# RobotCtrl_V2_Mother-board.net
KiCad netlist of a schematic drawn in Altium Designer
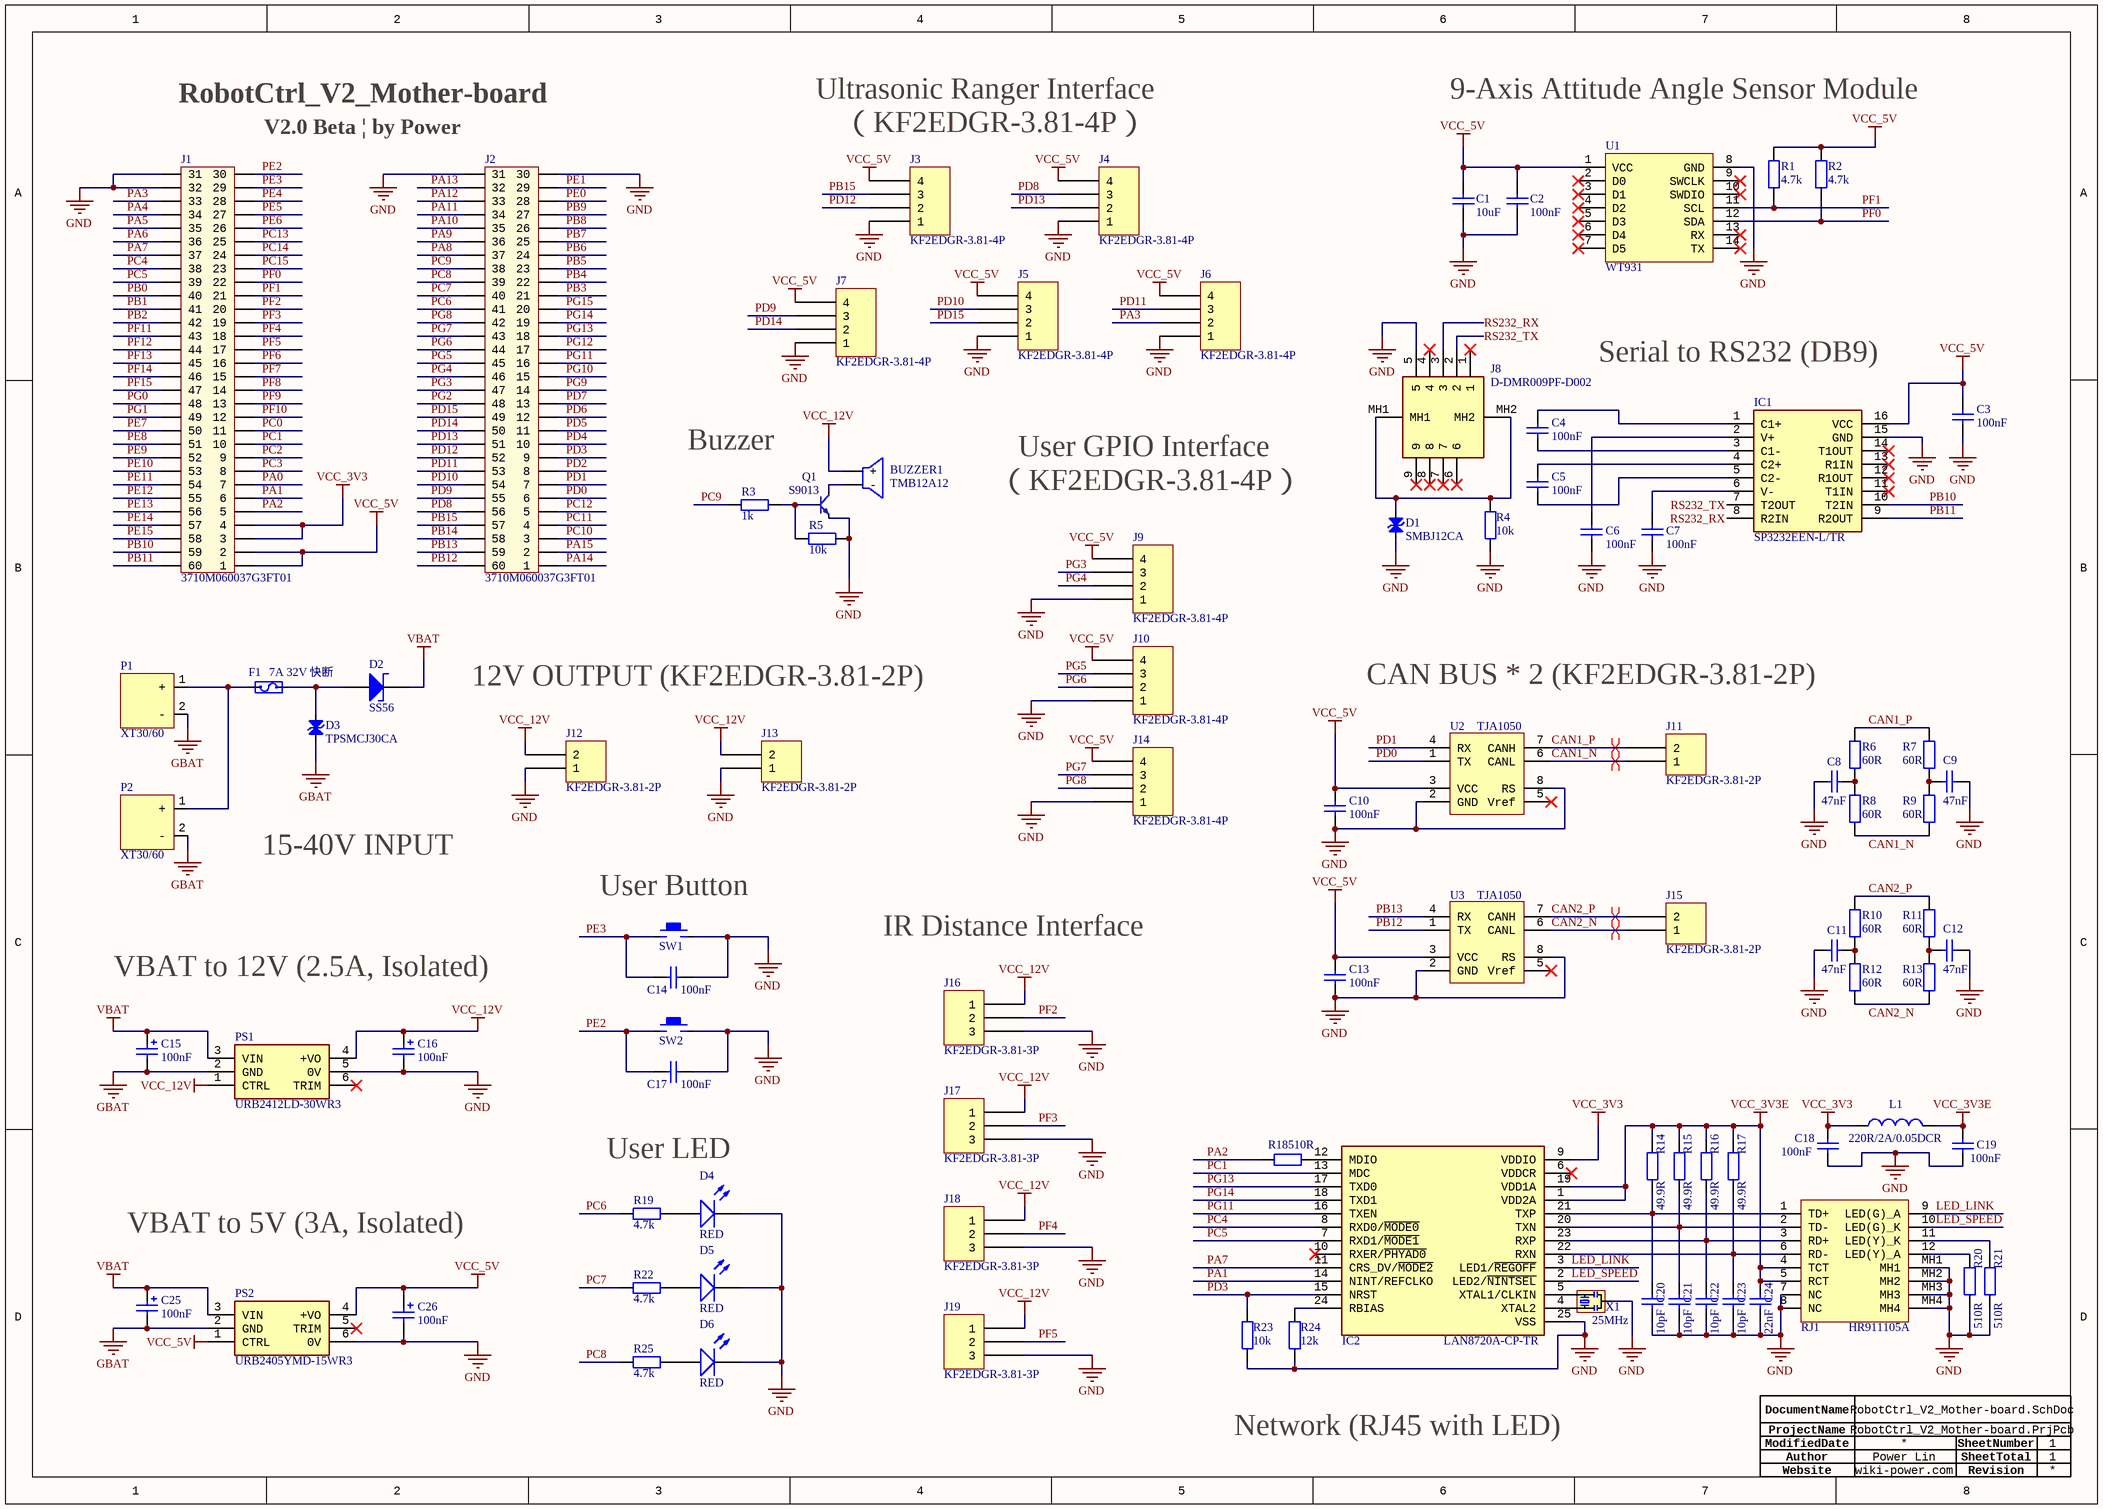
[diagram p0: RobotCtrl_V2_Mother-board.SchDoc]

(export (version "E")
  (design (tool "Eeschema 10.0.6"))
  (components
    (comp (ref "BUZZER1")
      (value "TMB12A12")
      (footprint "DIP,P=7.6mm")
      (description "TMB12A12 有源蜂鸣器")
      (libsource (lib "Power_Lib_Altium") (part "BUZZER"))
    )
    (comp (ref "C1")
      (value "10uF")
      (footprint "CAP-0603")
      (description "贴片电容")
      (libsource (lib "Power_Lib_Altium") (part "CAP"))
    )
    (comp (ref "C2")
      (value "100nF")
      (footprint "CAP-0603")
      (description "贴片电容")
      (libsource (lib "Power_Lib_Altium") (part "CAP"))
    )
    (comp (ref "C3")
      (value "100nF")
      (footprint "CAP-0603")
      (description "贴片电容")
      (libsource (lib "Power_Lib_Altium") (part "CAP"))
    )
    (comp (ref "C4")
      (value "100nF")
      (footprint "CAP-0603")
      (description "贴片电容")
      (libsource (lib "Power_Lib_Altium") (part "CAP"))
    )
    (comp (ref "C5")
      (value "100nF")
      (footprint "CAP-0603")
      (description "贴片电容")
      (libsource (lib "Power_Lib_Altium") (part "CAP"))
    )
    (comp (ref "C6")
      (value "100nF")
      (footprint "CAP-0603")
      (description "贴片电容")
      (libsource (lib "Power_Lib_Altium") (part "CAP"))
    )
    (comp (ref "C7")
      (value "100nF")
      (footprint "CAP-0603")
      (description "贴片电容")
      (libsource (lib "Power_Lib_Altium") (part "CAP"))
    )
    (comp (ref "C8")
      (value "47nF")
      (footprint "CAP-0603")
      (description "贴片电容")
      (libsource (lib "Power_Lib_Altium") (part "CAP"))
    )
    (comp (ref "C9")
      (value "47nF")
      (footprint "CAP-0603")
      (description "贴片电容")
      (libsource (lib "Power_Lib_Altium") (part "CAP"))
    )
    (comp (ref "C10")
      (value "100nF")
      (footprint "CAP-0603")
      (description "贴片电容")
      (libsource (lib "Power_Lib_Altium") (part "CAP"))
    )
    (comp (ref "C11")
      (value "47nF")
      (footprint "CAP-0603")
      (description "贴片电容")
      (libsource (lib "Power_Lib_Altium") (part "CAP"))
    )
    (comp (ref "C12")
      (value "47nF")
      (footprint "CAP-0603")
      (description "贴片电容")
      (libsource (lib "Power_Lib_Altium") (part "CAP"))
    )
    (comp (ref "C13")
      (value "100nF")
      (footprint "CAP-0603")
      (description "贴片电容")
      (libsource (lib "Power_Lib_Altium") (part "CAP"))
    )
    (comp (ref "C14")
      (value "100nF")
      (footprint "CAP-0603")
      (description "贴片电容")
      (libsource (lib "Power_Lib_Altium") (part "CAP"))
    )
    (comp (ref "C15")
      (value "100nF")
      (footprint "CAP-AUX-3216")
      (description "KM101M050F115A")
      (libsource (lib "Power_Lib_Altium") (part "CAP-POL"))
    )
    (comp (ref "C16")
      (value "100nF")
      (footprint "CAP-AUX-3216")
      (description "KM101M050F115A")
      (libsource (lib "Power_Lib_Altium") (part "CAP-POL"))
    )
    (comp (ref "C17")
      (value "100nF")
      (footprint "CAP-0603")
      (description "贴片电容")
      (libsource (lib "Power_Lib_Altium") (part "CAP"))
    )
    (comp (ref "C18")
      (value "100nF")
      (footprint "CAP-0603")
      (description "贴片电容")
      (libsource (lib "Power_Lib_Altium") (part "CAP"))
    )
    (comp (ref "C19")
      (value "100nF")
      (footprint "CAP-0603")
      (description "贴片电容")
      (libsource (lib "Power_Lib_Altium") (part "CAP"))
    )
    (comp (ref "C20")
      (value "10pF")
      (footprint "CAP-0603")
      (description "贴片电容")
      (libsource (lib "Power_Lib_Altium") (part "CAP"))
    )
    (comp (ref "C21")
      (value "10pF")
      (footprint "CAP-0603")
      (description "贴片电容")
      (libsource (lib "Power_Lib_Altium") (part "CAP"))
    )
    (comp (ref "C22")
      (value "10pF")
      (footprint "CAP-0603")
      (description "贴片电容")
      (libsource (lib "Power_Lib_Altium") (part "CAP"))
    )
    (comp (ref "C23")
      (value "10pF")
      (footprint "CAP-0603")
      (description "贴片电容")
      (libsource (lib "Power_Lib_Altium") (part "CAP"))
    )
    (comp (ref "C24")
      (value "22nF")
      (footprint "CAP-0603")
      (description "贴片电容")
      (libsource (lib "Power_Lib_Altium") (part "CAP"))
    )
    (comp (ref "C25")
      (value "100nF")
      (footprint "CAP-AUX-3216")
      (description "KM101M050F115A")
      (libsource (lib "Power_Lib_Altium") (part "CAP-POL"))
    )
    (comp (ref "C26")
      (value "100nF")
      (footprint "CAP-AUX-3216")
      (description "KM101M050F115A")
      (libsource (lib "Power_Lib_Altium") (part "CAP-POL"))
    )
    (comp (ref "D1")
      (value "SMBJ12CA")
      (footprint "DO-214AA/SMB")
      (libsource (lib "Power_Lib_Altium") (part "TVS_C"))
    )
    (comp (ref "D2")
      (value "SS56")
      (footprint "DO-214AB/SMC")
      (description "肖特基二极管")
      (libsource (lib "Power_Lib_Altium") (part "DIODE_Schottky"))
    )
    (comp (ref "D3")
      (value "TPSMCJ30CA")
      (footprint "DO-214AB/SMC")
      (libsource (lib "Power_Lib_Altium") (part "TVS_C"))
    )
    (comp (ref "D4")
      (value "RED")
      (footprint "LED-0603")
      (description "发光二极管")
      (libsource (lib "Power_Lib_Altium") (part "LED"))
    )
    (comp (ref "D5")
      (value "RED")
      (footprint "LED-0603")
      (description "发光二极管")
      (libsource (lib "Power_Lib_Altium") (part "LED"))
    )
    (comp (ref "D6")
      (value "RED")
      (footprint "LED-0603")
      (description "发光二极管")
      (libsource (lib "Power_Lib_Altium") (part "LED"))
    )
    (comp (ref "F1")
      (value "7A 32V 快断")
      (footprint "FUSE_1206")
      (description "0437007.WR")
      (libsource (lib "Power_Lib_Altium") (part "Fuse"))
    )
    (comp (ref "IC1")
      (value "SP3232EEN-L/TR")
      (footprint "SOIC-16_150mil")
      (description "RS232 芯片")
      (fields (field (name "MOUSER PART NUMBER") "701-SP3232EEN-L/TR"))
      (libsource (lib "Power_Lib_Altium") (part "SP3232EEN"))
    )
    (comp (ref "IC2")
      (value "LAN8720A-CP-TR")
      (footprint "QFN-24-4x4")
      (description "Integrated Circuit")
      (fields (field (name "MOUSER PART NUMBER") "886-LAN8720A-CP-TR"))
      (libsource (lib "Power_Lib_Altium") (part "LAN8720A-CP-TR"))
    )
    (comp (ref "J1")
      (value "3710M060037G3FT01")
      (footprint "3710M060037G3FT01")
      (description "B2B Connector")
      (libsource (lib "Power_Lib_Altium") (part "3710M/F"))
    )
    (comp (ref "J2")
      (value "3710M060037G3FT01")
      (footprint "3710M060037G3FT01")
      (description "B2B Connector")
      (libsource (lib "Power_Lib_Altium") (part "3710M/F"))
    )
    (comp (ref "J3")
      (value "KF2EDGR-3.81-4P")
      (footprint "FCI 06-381-4PIN")
      (description "TERM BLOCK HDR 4POS 90DEG 3.81MM")
      (fields (field (name "PART NUMBER") "OQ0432510000G") (field (name "MANUFACTURER") "Amphenol Anytek"))
      (libsource (lib "Power_Lib_Altium") (part "KF2EDGR-3.81-4P"))
    )
    (comp (ref "J4")
      (value "KF2EDGR-3.81-4P")
      (footprint "FCI 06-381-4PIN")
      (description "TERM BLOCK HDR 4POS 90DEG 3.81MM")
      (fields (field (name "PART NUMBER") "OQ0432510000G") (field (name "MANUFACTURER") "Amphenol Anytek"))
      (libsource (lib "Power_Lib_Altium") (part "KF2EDGR-3.81-4P"))
    )
    (comp (ref "J5")
      (value "KF2EDGR-3.81-4P")
      (footprint "FCI 06-381-4PIN")
      (description "TERM BLOCK HDR 4POS 90DEG 3.81MM")
      (fields (field (name "PART NUMBER") "OQ0432510000G") (field (name "MANUFACTURER") "Amphenol Anytek"))
      (libsource (lib "Power_Lib_Altium") (part "KF2EDGR-3.81-4P"))
    )
    (comp (ref "J6")
      (value "KF2EDGR-3.81-4P")
      (footprint "FCI 06-381-4PIN")
      (description "TERM BLOCK HDR 4POS 90DEG 3.81MM")
      (fields (field (name "PART NUMBER") "OQ0432510000G") (field (name "MANUFACTURER") "Amphenol Anytek"))
      (libsource (lib "Power_Lib_Altium") (part "KF2EDGR-3.81-4P"))
    )
    (comp (ref "J7")
      (value "KF2EDGR-3.81-4P")
      (footprint "FCI 06-381-4PIN")
      (description "TERM BLOCK HDR 4POS 90DEG 3.81MM")
      (fields (field (name "PART NUMBER") "OQ0432510000G") (field (name "MANUFACTURER") "Amphenol Anytek"))
      (libsource (lib "Power_Lib_Altium") (part "KF2EDGR-3.81-4P"))
    )
    (comp (ref "J8")
      (value "D-DMR009PF-D002")
      (footprint "Through Hole,P=2.77mm")
      (description "D-Sub 连接器")
      (fields
        (field (name "MANUFACTURER_PART_NUMBER") "5747844-5")
        (field (name "MOUSER PART NUMBER") "571-5747844-5")
      )
      (libsource (lib "Power_Lib_Altium") (part "DB9"))
    )
    (comp (ref "J9")
      (value "KF2EDGR-3.81-4P")
      (footprint "FCI 06-381-4PIN")
      (description "TERM BLOCK HDR 4POS 90DEG 3.81MM")
      (fields (field (name "PART NUMBER") "OQ0432510000G") (field (name "MANUFACTURER") "Amphenol Anytek"))
      (libsource (lib "Power_Lib_Altium") (part "KF2EDGR-3.81-4P"))
    )
    (comp (ref "J10")
      (value "KF2EDGR-3.81-4P")
      (footprint "FCI 06-381-4PIN")
      (description "TERM BLOCK HDR 4POS 90DEG 3.81MM")
      (fields (field (name "PART NUMBER") "OQ0432510000G") (field (name "MANUFACTURER") "Amphenol Anytek"))
      (libsource (lib "Power_Lib_Altium") (part "KF2EDGR-3.81-4P"))
    )
    (comp (ref "J11")
      (value "KF2EDGR-3.81-2P")
      (footprint "FCI 06-381-2PIN")
      (description "TERM BLOCK HDR 2POS 90DEG 3.81MM")
      (fields (field (name "PART NUMBER") "OQ0232510000G") (field (name "MANUFACTURER") "Amphenol Anytek"))
      (libsource (lib "Power_Lib_Altium") (part "KF2EDGR-3.81-2P"))
    )
    (comp (ref "J12")
      (value "KF2EDGR-3.81-2P")
      (footprint "FCI 06-381-2PIN")
      (description "TERM BLOCK HDR 2POS 90DEG 3.81MM")
      (fields (field (name "PART NUMBER") "OQ0232510000G") (field (name "MANUFACTURER") "Amphenol Anytek"))
      (libsource (lib "Power_Lib_Altium") (part "KF2EDGR-3.81-2P"))
    )
    (comp (ref "J13")
      (value "KF2EDGR-3.81-2P")
      (footprint "FCI 06-381-2PIN")
      (description "TERM BLOCK HDR 2POS 90DEG 3.81MM")
      (fields (field (name "PART NUMBER") "OQ0232510000G") (field (name "MANUFACTURER") "Amphenol Anytek"))
      (libsource (lib "Power_Lib_Altium") (part "KF2EDGR-3.81-2P"))
    )
    (comp (ref "J14")
      (value "KF2EDGR-3.81-4P")
      (footprint "FCI 06-381-4PIN")
      (description "TERM BLOCK HDR 4POS 90DEG 3.81MM")
      (fields (field (name "PART NUMBER") "OQ0432510000G") (field (name "MANUFACTURER") "Amphenol Anytek"))
      (libsource (lib "Power_Lib_Altium") (part "KF2EDGR-3.81-4P"))
    )
    (comp (ref "J15")
      (value "KF2EDGR-3.81-2P")
      (footprint "FCI 06-381-2PIN")
      (description "TERM BLOCK HDR 2POS 90DEG 3.81MM")
      (fields (field (name "PART NUMBER") "OQ0232510000G") (field (name "MANUFACTURER") "Amphenol Anytek"))
      (libsource (lib "Power_Lib_Altium") (part "KF2EDGR-3.81-2P"))
    )
    (comp (ref "J16")
      (value "KF2EDGR-3.81-3P")
      (footprint "FCI 06-381-3PIN")
      (description "TERM BLOCK HDR 3POS 90DEG 3.81MM")
      (fields (field (name "MANUFACTURER") "Amphenol Anytek") (field (name "PART NUMBER") "OQ0332510000G"))
      (libsource (lib "Power_Lib_Altium") (part "KF2EDGR-3.81-3P"))
    )
    (comp (ref "J17")
      (value "KF2EDGR-3.81-3P")
      (footprint "FCI 06-381-3PIN")
      (description "TERM BLOCK HDR 3POS 90DEG 3.81MM")
      (fields (field (name "MANUFACTURER") "Amphenol Anytek") (field (name "PART NUMBER") "OQ0332510000G"))
      (libsource (lib "Power_Lib_Altium") (part "KF2EDGR-3.81-3P"))
    )
    (comp (ref "J18")
      (value "KF2EDGR-3.81-3P")
      (footprint "FCI 06-381-3PIN")
      (description "TERM BLOCK HDR 3POS 90DEG 3.81MM")
      (fields (field (name "MANUFACTURER") "Amphenol Anytek") (field (name "PART NUMBER") "OQ0332510000G"))
      (libsource (lib "Power_Lib_Altium") (part "KF2EDGR-3.81-3P"))
    )
    (comp (ref "J19")
      (value "KF2EDGR-3.81-3P")
      (footprint "FCI 06-381-3PIN")
      (description "TERM BLOCK HDR 3POS 90DEG 3.81MM")
      (fields (field (name "MANUFACTURER") "Amphenol Anytek") (field (name "PART NUMBER") "OQ0332510000G"))
      (libsource (lib "Power_Lib_Altium") (part "KF2EDGR-3.81-3P"))
    )
    (comp (ref "L1")
      (value "220R/2A/0.05DCR")
      (footprint "L-0603")
      (description "BLM18KG221SN1D")
      (libsource (lib "Power_Lib_Altium") (part "BEAD"))
    )
    (comp (ref "P1")
      (value "XT30/60")
      (footprint "XT60PW-M")
      (libsource (lib "Power_Lib_Altium") (part "XT30/60"))
    )
    (comp (ref "P2")
      (value "XT30/60")
      (footprint "XT60PW-M")
      (libsource (lib "Power_Lib_Altium") (part "XT30/60"))
    )
    (comp (ref "PS1")
      (value "URB2412LD-30WR3")
      (footprint "URB2412LD30WR3")
      (description "金升阳隔离电源")
      (fields (field (name "MANUFACTURER_PART_NUMBER") "URB2412LD-30WHR3"))
      (libsource (lib "Power_Lib_Altium") (part "URB2412LD-30WR3"))
    )
    (comp (ref "PS2")
      (value "URB2405YMD-15WR3")
      (footprint "URB2405YMD15WR3")
      (description "金升阳隔离电源")
      (fields (field (name "MANUFACTURER_PART_NUMBER") "URB2405YMD-10WR3"))
      (libsource (lib "Power_Lib_Altium") (part "URB2405YMD-15WR3"))
    )
    (comp (ref "Q1")
      (value "S9013")
      (footprint "SOT-23-3")
      (libsource (lib "Power_Lib_Altium") (part "BJT_NPN"))
    )
    (comp (ref "R1")
      (value "4.7k")
      (footprint "R-0603")
      (description "贴片电阻")
      (libsource (lib "") (part "RES_1"))
    )
    (comp (ref "R2")
      (value "4.7k")
      (footprint "R-0603")
      (description "贴片电阻")
      (libsource (lib "") (part "RES_1"))
    )
    (comp (ref "R3")
      (value "1k")
      (footprint "R-0603")
      (description "贴片电阻")
      (libsource (lib "") (part "RES_3"))
    )
    (comp (ref "R4")
      (value "10k")
      (footprint "R-0603")
      (description "贴片电阻")
      (libsource (lib "") (part "RES_1"))
    )
    (comp (ref "R5")
      (value "10k")
      (footprint "R-0603")
      (description "贴片电阻")
      (libsource (lib "") (part "RES_2"))
    )
    (comp (ref "R6")
      (value "60R")
      (footprint "R-0603")
      (description "贴片电阻")
      (libsource (lib "Power_Lib_Altium") (part "RES"))
    )
    (comp (ref "R7")
      (value "60R")
      (footprint "R-0603")
      (description "贴片电阻")
      (libsource (lib "") (part "RES_1"))
    )
    (comp (ref "R8")
      (value "60R")
      (footprint "R-0603")
      (description "贴片电阻")
      (libsource (lib "Power_Lib_Altium") (part "RES"))
    )
    (comp (ref "R9")
      (value "60R")
      (footprint "R-0603")
      (description "贴片电阻")
      (libsource (lib "") (part "RES_1"))
    )
    (comp (ref "R10")
      (value "60R")
      (footprint "R-0603")
      (description "贴片电阻")
      (libsource (lib "Power_Lib_Altium") (part "RES"))
    )
    (comp (ref "R11")
      (value "60R")
      (footprint "R-0603")
      (description "贴片电阻")
      (libsource (lib "") (part "RES_1"))
    )
    (comp (ref "R12")
      (value "60R")
      (footprint "R-0603")
      (description "贴片电阻")
      (libsource (lib "Power_Lib_Altium") (part "RES"))
    )
    (comp (ref "R13")
      (value "60R")
      (footprint "R-0603")
      (description "贴片电阻")
      (libsource (lib "") (part "RES_1"))
    )
    (comp (ref "R14")
      (value "49.9R")
      (footprint "R-0603")
      (description "贴片电阻")
      (libsource (lib "") (part "RES_1"))
    )
    (comp (ref "R15")
      (value "49.9R")
      (footprint "R-0603")
      (description "贴片电阻")
      (libsource (lib "") (part "RES_1"))
    )
    (comp (ref "R16")
      (value "49.9R")
      (footprint "R-0603")
      (description "贴片电阻")
      (libsource (lib "") (part "RES_1"))
    )
    (comp (ref "R17")
      (value "49.9R")
      (footprint "R-0603")
      (description "贴片电阻")
      (libsource (lib "") (part "RES_1"))
    )
    (comp (ref "R18")
      (value "510R")
      (footprint "R-0603")
      (description "贴片电阻")
      (libsource (lib "") (part "RES_2"))
    )
    (comp (ref "R19")
      (value "4.7k")
      (footprint "R-0603")
      (description "贴片电阻")
      (libsource (lib "") (part "RES_2"))
    )
    (comp (ref "R20")
      (value "510R")
      (footprint "R-0603")
      (description "贴片电阻")
      (libsource (lib "") (part "RES_1"))
    )
    (comp (ref "R21")
      (value "510R")
      (footprint "R-0603")
      (description "贴片电阻")
      (libsource (lib "") (part "RES_1"))
    )
    (comp (ref "R22")
      (value "4.7k")
      (footprint "R-0603")
      (description "贴片电阻")
      (libsource (lib "") (part "RES_2"))
    )
    (comp (ref "R23")
      (value "10k")
      (footprint "R-0603")
      (description "贴片电阻")
      (libsource (lib "Power_Lib_Altium") (part "RES"))
    )
    (comp (ref "R24")
      (value "12k")
      (footprint "R-0603")
      (description "贴片电阻")
      (libsource (lib "Power_Lib_Altium") (part "RES"))
    )
    (comp (ref "R25")
      (value "4.7k")
      (footprint "R-0603")
      (description "贴片电阻")
      (libsource (lib "") (part "RES_2"))
    )
    (comp (ref "RJ1")
      (value "HR911105A")
      (footprint "HR911105A")
      (libsource (lib "Power_Lib_Altium") (part "RJ45_LED"))
    )
    (comp (ref "SW1")
      (value "KEY")
      (footprint "KEY-4P-4.2*3.4*2.5")
      (description "按键开关")
      (libsource (lib "Power_Lib_Altium") (part "KEY"))
    )
    (comp (ref "SW2")
      (value "KEY")
      (footprint "KEY-4P-4.2*3.4*2.5")
      (description "按键开关")
      (libsource (lib "Power_Lib_Altium") (part "KEY"))
    )
    (comp (ref "U1")
      (value "WT931")
      (footprint "WT931")
      (description "陀螺仪模组")
      (libsource (lib "Power_Lib_Altium") (part "WT931"))
    )
    (comp (ref "U2")
      (value "TJA1050")
      (footprint "SOIC_8")
      (description "CAN 控制器（5V）")
      (libsource (lib "Power_Lib_Altium") (part "TJA1050"))
    )
    (comp (ref "U3")
      (value "TJA1050")
      (footprint "SOIC_8")
      (description "CAN 控制器（5V）")
      (libsource (lib "Power_Lib_Altium") (part "TJA1050"))
    )
    (comp (ref "X1")
      (value "25MHz")
      (footprint "SMD3213-3P")
      (description "CSTCE25M00G51-R0")
      (libsource (lib "Power_Lib_Altium") (part "XTAL"))
    )
  )
  (nets
    (net (code "1") (name "/CAN1_N") (class "Default")
      (node (ref "J11") (pin "1") (pinfunction "1_1") (pintype "passive"))
      (node (ref "R8") (pin "2") (pinfunction "2_2") (pintype "passive"))
      (node (ref "R9") (pin "1") (pinfunction "1_1") (pintype "passive"))
      (node (ref "U2") (pin "6") (pinfunction "CANL_6") (pintype "passive"))
    )
    (net (code "2") (name "/CAN1_P") (class "Default")
      (node (ref "J11") (pin "2") (pinfunction "2_2") (pintype "passive"))
      (node (ref "R6") (pin "1") (pinfunction "1_1") (pintype "passive"))
      (node (ref "R7") (pin "2") (pinfunction "2_2") (pintype "passive"))
      (node (ref "U2") (pin "7") (pinfunction "CANH_7") (pintype "passive"))
    )
    (net (code "3") (name "/CAN2_N") (class "Default")
      (node (ref "J15") (pin "1") (pinfunction "1_1") (pintype "passive"))
      (node (ref "R12") (pin "2") (pinfunction "2_2") (pintype "passive"))
      (node (ref "R13") (pin "1") (pinfunction "1_1") (pintype "passive"))
      (node (ref "U3") (pin "6") (pinfunction "CANL_6") (pintype "passive"))
    )
    (net (code "4") (name "/CAN2_P") (class "Default")
      (node (ref "J15") (pin "2") (pinfunction "2_2") (pintype "passive"))
      (node (ref "R10") (pin "1") (pinfunction "1_1") (pintype "passive"))
      (node (ref "R11") (pin "2") (pinfunction "2_2") (pintype "passive"))
      (node (ref "U3") (pin "7") (pinfunction "CANH_7") (pintype "passive"))
    )
    (net (code "5") (name "/LED_LINK") (class "Default")
      (node (ref "IC2") (pin "3") (pinfunction "LED1/~{REGOFF}_3") (pintype "passive"))
      (node (ref "RJ1") (pin "9") (pinfunction "LED(G)_A_9") (pintype "passive"))
    )
    (net (code "6") (name "/LED_SPEED") (class "Default")
      (node (ref "IC2") (pin "2") (pinfunction "LED2/~{NINTSEL}_2") (pintype "passive"))
      (node (ref "RJ1") (pin "10") (pinfunction "LED(G)_K_10") (pintype "passive"))
    )
    (net (code "7") (name "/PA0") (class "Default")
      (node (ref "J1") (pin "7") (pinfunction "7_7") (pintype "passive"))
    )
    (net (code "8") (name "/PA1") (class "Default")
      (node (ref "IC2") (pin "14") (pinfunction "NINT/REFCLKO_14") (pintype "passive"))
      (node (ref "J1") (pin "6") (pinfunction "6_6") (pintype "passive"))
    )
    (net (code "9") (name "/PA2") (class "Default")
      (node (ref "J1") (pin "5") (pinfunction "5_5") (pintype "passive"))
      (node (ref "R18") (pin "2") (pinfunction "2_2") (pintype "passive"))
    )
    (net (code "10") (name "/PA3") (class "Default")
      (node (ref "J1") (pin "33") (pinfunction "33_33") (pintype "passive"))
      (node (ref "J6") (pin "2") (pinfunction "2_2") (pintype "passive"))
    )
    (net (code "11") (name "/PA4") (class "Default")
      (node (ref "J1") (pin "34") (pinfunction "34_34") (pintype "passive"))
    )
    (net (code "12") (name "/PA5") (class "Default")
      (node (ref "J1") (pin "35") (pinfunction "35_35") (pintype "passive"))
    )
    (net (code "13") (name "/PA6") (class "Default")
      (node (ref "J1") (pin "36") (pinfunction "36_36") (pintype "passive"))
    )
    (net (code "14") (name "/PA7") (class "Default")
      (node (ref "IC2") (pin "11") (pinfunction "CRS_DV/~{MODE2}_11") (pintype "passive"))
      (node (ref "J1") (pin "37") (pinfunction "37_37") (pintype "passive"))
    )
    (net (code "15") (name "/PA8") (class "Default")
      (node (ref "J2") (pin "37") (pinfunction "37_37") (pintype "passive"))
    )
    (net (code "16") (name "/PA9") (class "Default")
      (node (ref "J2") (pin "36") (pinfunction "36_36") (pintype "passive"))
    )
    (net (code "17") (name "/PA10") (class "Default")
      (node (ref "J2") (pin "35") (pinfunction "35_35") (pintype "passive"))
    )
    (net (code "18") (name "/PA11") (class "Default")
      (node (ref "J2") (pin "34") (pinfunction "34_34") (pintype "passive"))
    )
    (net (code "19") (name "/PA12") (class "Default")
      (node (ref "J2") (pin "33") (pinfunction "33_33") (pintype "passive"))
    )
    (net (code "20") (name "/PA13") (class "Default")
      (node (ref "J2") (pin "32") (pinfunction "32_32") (pintype "passive"))
    )
    (net (code "21") (name "/PA14") (class "Default")
      (node (ref "J2") (pin "1") (pinfunction "1_1") (pintype "passive"))
    )
    (net (code "22") (name "/PA15") (class "Default")
      (node (ref "J2") (pin "2") (pinfunction "2_2") (pintype "passive"))
    )
    (net (code "23") (name "/PB0") (class "Default")
      (node (ref "J1") (pin "40") (pinfunction "40_40") (pintype "passive"))
    )
    (net (code "24") (name "/PB1") (class "Default")
      (node (ref "J1") (pin "41") (pinfunction "41_41") (pintype "passive"))
    )
    (net (code "25") (name "/PB2") (class "Default")
      (node (ref "J1") (pin "42") (pinfunction "42_42") (pintype "passive"))
    )
    (net (code "26") (name "/PB3") (class "Default")
      (node (ref "J2") (pin "21") (pinfunction "21_21") (pintype "passive"))
    )
    (net (code "27") (name "/PB4") (class "Default")
      (node (ref "J2") (pin "22") (pinfunction "22_22") (pintype "passive"))
    )
    (net (code "28") (name "/PB5") (class "Default")
      (node (ref "J2") (pin "23") (pinfunction "23_23") (pintype "passive"))
    )
    (net (code "29") (name "/PB6") (class "Default")
      (node (ref "J2") (pin "24") (pinfunction "24_24") (pintype "passive"))
    )
    (net (code "30") (name "/PB7") (class "Default")
      (node (ref "J2") (pin "25") (pinfunction "25_25") (pintype "passive"))
    )
    (net (code "31") (name "/PB8") (class "Default")
      (node (ref "J2") (pin "26") (pinfunction "26_26") (pintype "passive"))
    )
    (net (code "32") (name "/PB9") (class "Default")
      (node (ref "J2") (pin "27") (pinfunction "27_27") (pintype "passive"))
    )
    (net (code "33") (name "/PB10") (class "Default")
      (node (ref "IC1") (pin "10") (pinfunction "T2IN_10") (pintype "passive"))
      (node (ref "J1") (pin "59") (pinfunction "59_59") (pintype "passive"))
    )
    (net (code "34") (name "/PB11") (class "Default")
      (node (ref "IC1") (pin "9") (pinfunction "R2OUT_9") (pintype "passive"))
      (node (ref "J1") (pin "60") (pinfunction "60_60") (pintype "passive"))
    )
    (net (code "35") (name "/PB12") (class "Default")
      (node (ref "J2") (pin "60") (pinfunction "60_60") (pintype "passive"))
      (node (ref "U3") (pin "1") (pinfunction "TX_1") (pintype "passive"))
    )
    (net (code "36") (name "/PB13") (class "Default")
      (node (ref "J2") (pin "59") (pinfunction "59_59") (pintype "passive"))
      (node (ref "U3") (pin "4") (pinfunction "RX_4") (pintype "passive"))
    )
    (net (code "37") (name "/PB14") (class "Default")
      (node (ref "J2") (pin "58") (pinfunction "58_58") (pintype "passive"))
    )
    (net (code "38") (name "/PB15") (class "Default")
      (node (ref "J2") (pin "57") (pinfunction "57_57") (pintype "passive"))
      (node (ref "J3") (pin "3") (pinfunction "3_3") (pintype "passive"))
    )
    (net (code "39") (name "/PC0") (class "Default")
      (node (ref "J1") (pin "11") (pinfunction "11_11") (pintype "passive"))
    )
    (net (code "40") (name "/PC1") (class "Default")
      (node (ref "IC2") (pin "13") (pinfunction "MDC_13") (pintype "passive"))
      (node (ref "J1") (pin "10") (pinfunction "10_10") (pintype "passive"))
    )
    (net (code "41") (name "/PC2") (class "Default")
      (node (ref "J1") (pin "9") (pinfunction "9_9") (pintype "passive"))
    )
    (net (code "42") (name "/PC3") (class "Default")
      (node (ref "J1") (pin "8") (pinfunction "8_8") (pintype "passive"))
    )
    (net (code "43") (name "/PC4") (class "Default")
      (node (ref "IC2") (pin "8") (pinfunction "RXD0/~{MODE0}_8") (pintype "passive"))
      (node (ref "J1") (pin "38") (pinfunction "38_38") (pintype "passive"))
    )
    (net (code "44") (name "/PC5") (class "Default")
      (node (ref "IC2") (pin "7") (pinfunction "RXD1/~{MODE1}_7") (pintype "passive"))
      (node (ref "J1") (pin "39") (pinfunction "39_39") (pintype "passive"))
    )
    (net (code "45") (name "/PC6") (class "Default")
      (node (ref "J2") (pin "41") (pinfunction "41_41") (pintype "passive"))
      (node (ref "R19") (pin "2") (pinfunction "2_2") (pintype "passive"))
    )
    (net (code "46") (name "/PC7") (class "Default")
      (node (ref "J2") (pin "40") (pinfunction "40_40") (pintype "passive"))
      (node (ref "R22") (pin "2") (pinfunction "2_2") (pintype "passive"))
    )
    (net (code "47") (name "/PC8") (class "Default")
      (node (ref "J2") (pin "39") (pinfunction "39_39") (pintype "passive"))
      (node (ref "R25") (pin "2") (pinfunction "2_2") (pintype "passive"))
    )
    (net (code "48") (name "/PC9") (class "Default")
      (node (ref "J2") (pin "38") (pinfunction "38_38") (pintype "passive"))
      (node (ref "R3") (pin "1") (pinfunction "1_1") (pintype "passive"))
    )
    (net (code "49") (name "/PC10") (class "Default")
      (node (ref "J2") (pin "3") (pinfunction "3_3") (pintype "passive"))
    )
    (net (code "50") (name "/PC11") (class "Default")
      (node (ref "J2") (pin "4") (pinfunction "4_4") (pintype "passive"))
    )
    (net (code "51") (name "/PC12") (class "Default")
      (node (ref "J2") (pin "5") (pinfunction "5_5") (pintype "passive"))
    )
    (net (code "52") (name "/PC13") (class "Default")
      (node (ref "J1") (pin "25") (pinfunction "25_25") (pintype "passive"))
    )
    (net (code "53") (name "/PC14") (class "Default")
      (node (ref "J1") (pin "24") (pinfunction "24_24") (pintype "passive"))
    )
    (net (code "54") (name "/PC15") (class "Default")
      (node (ref "J1") (pin "23") (pinfunction "23_23") (pintype "passive"))
    )
    (net (code "55") (name "/PD0") (class "Default")
      (node (ref "J2") (pin "6") (pinfunction "6_6") (pintype "passive"))
      (node (ref "U2") (pin "1") (pinfunction "TX_1") (pintype "passive"))
    )
    (net (code "56") (name "/PD1") (class "Default")
      (node (ref "J2") (pin "7") (pinfunction "7_7") (pintype "passive"))
      (node (ref "U2") (pin "4") (pinfunction "RX_4") (pintype "passive"))
    )
    (net (code "57") (name "/PD2") (class "Default")
      (node (ref "J2") (pin "8") (pinfunction "8_8") (pintype "passive"))
    )
    (net (code "58") (name "/PD3") (class "Default")
      (node (ref "IC2") (pin "15") (pinfunction "NRST_15") (pintype "passive"))
      (node (ref "J2") (pin "9") (pinfunction "9_9") (pintype "passive"))
      (node (ref "R23") (pin "1") (pinfunction "1_1") (pintype "passive"))
    )
    (net (code "59") (name "/PD4") (class "Default")
      (node (ref "J2") (pin "10") (pinfunction "10_10") (pintype "passive"))
    )
    (net (code "60") (name "/PD5") (class "Default")
      (node (ref "J2") (pin "11") (pinfunction "11_11") (pintype "passive"))
    )
    (net (code "61") (name "/PD6") (class "Default")
      (node (ref "J2") (pin "12") (pinfunction "12_12") (pintype "passive"))
    )
    (net (code "62") (name "/PD7") (class "Default")
      (node (ref "J2") (pin "13") (pinfunction "13_13") (pintype "passive"))
    )
    (net (code "63") (name "/PD8") (class "Default")
      (node (ref "J2") (pin "56") (pinfunction "56_56") (pintype "passive"))
      (node (ref "J4") (pin "3") (pinfunction "3_3") (pintype "passive"))
    )
    (net (code "64") (name "/PD9") (class "Default")
      (node (ref "J2") (pin "55") (pinfunction "55_55") (pintype "passive"))
      (node (ref "J7") (pin "3") (pinfunction "3_3") (pintype "passive"))
    )
    (net (code "65") (name "/PD10") (class "Default")
      (node (ref "J2") (pin "54") (pinfunction "54_54") (pintype "passive"))
      (node (ref "J5") (pin "3") (pinfunction "3_3") (pintype "passive"))
    )
    (net (code "66") (name "/PD11") (class "Default")
      (node (ref "J2") (pin "53") (pinfunction "53_53") (pintype "passive"))
      (node (ref "J6") (pin "3") (pinfunction "3_3") (pintype "passive"))
    )
    (net (code "67") (name "/PD12") (class "Default")
      (node (ref "J2") (pin "52") (pinfunction "52_52") (pintype "passive"))
      (node (ref "J3") (pin "2") (pinfunction "2_2") (pintype "passive"))
    )
    (net (code "68") (name "/PD13") (class "Default")
      (node (ref "J2") (pin "51") (pinfunction "51_51") (pintype "passive"))
      (node (ref "J4") (pin "2") (pinfunction "2_2") (pintype "passive"))
    )
    (net (code "69") (name "/PD14") (class "Default")
      (node (ref "J2") (pin "50") (pinfunction "50_50") (pintype "passive"))
      (node (ref "J7") (pin "2") (pinfunction "2_2") (pintype "passive"))
    )
    (net (code "70") (name "/PD15") (class "Default")
      (node (ref "J2") (pin "49") (pinfunction "49_49") (pintype "passive"))
      (node (ref "J5") (pin "2") (pinfunction "2_2") (pintype "passive"))
    )
    (net (code "71") (name "/PE0") (class "Default")
      (node (ref "J2") (pin "28") (pinfunction "28_28") (pintype "passive"))
    )
    (net (code "72") (name "/PE1") (class "Default")
      (node (ref "J2") (pin "29") (pinfunction "29_29") (pintype "passive"))
    )
    (net (code "73") (name "/PE2") (class "Default")
      (node (ref "C17") (pin "2") (pinfunction "2_2") (pintype "passive"))
      (node (ref "J1") (pin "30") (pinfunction "30_30") (pintype "passive"))
      (node (ref "SW2") (pin "1") (pinfunction "1_1") (pintype "passive"))
    )
    (net (code "74") (name "/PE3") (class "Default")
      (node (ref "C14") (pin "2") (pinfunction "2_2") (pintype "passive"))
      (node (ref "J1") (pin "29") (pinfunction "29_29") (pintype "passive"))
      (node (ref "SW1") (pin "1") (pinfunction "1_1") (pintype "passive"))
    )
    (net (code "75") (name "/PE4") (class "Default")
      (node (ref "J1") (pin "28") (pinfunction "28_28") (pintype "passive"))
    )
    (net (code "76") (name "/PE5") (class "Default")
      (node (ref "J1") (pin "27") (pinfunction "27_27") (pintype "passive"))
    )
    (net (code "77") (name "/PE6") (class "Default")
      (node (ref "J1") (pin "26") (pinfunction "26_26") (pintype "passive"))
    )
    (net (code "78") (name "/PE7") (class "Default")
      (node (ref "J1") (pin "50") (pinfunction "50_50") (pintype "passive"))
    )
    (net (code "79") (name "/PE8") (class "Default")
      (node (ref "J1") (pin "51") (pinfunction "51_51") (pintype "passive"))
    )
    (net (code "80") (name "/PE9") (class "Default")
      (node (ref "J1") (pin "52") (pinfunction "52_52") (pintype "passive"))
    )
    (net (code "81") (name "/PE10") (class "Default")
      (node (ref "J1") (pin "53") (pinfunction "53_53") (pintype "passive"))
    )
    (net (code "82") (name "/PE11") (class "Default")
      (node (ref "J1") (pin "54") (pinfunction "54_54") (pintype "passive"))
    )
    (net (code "83") (name "/PE12") (class "Default")
      (node (ref "J1") (pin "55") (pinfunction "55_55") (pintype "passive"))
    )
    (net (code "84") (name "/PE13") (class "Default")
      (node (ref "J1") (pin "56") (pinfunction "56_56") (pintype "passive"))
    )
    (net (code "85") (name "/PE14") (class "Default")
      (node (ref "J1") (pin "57") (pinfunction "57_57") (pintype "passive"))
    )
    (net (code "86") (name "/PE15") (class "Default")
      (node (ref "J1") (pin "58") (pinfunction "58_58") (pintype "passive"))
    )
    (net (code "87") (name "/PF0") (class "Default")
      (node (ref "J1") (pin "22") (pinfunction "22_22") (pintype "passive"))
      (node (ref "R2") (pin "1") (pinfunction "1_1") (pintype "passive"))
      (node (ref "U1") (pin "12") (pinfunction "SDA_12") (pintype "passive"))
    )
    (net (code "88") (name "/PF1") (class "Default")
      (node (ref "J1") (pin "21") (pinfunction "21_21") (pintype "passive"))
      (node (ref "R1") (pin "1") (pinfunction "1_1") (pintype "passive"))
      (node (ref "U1") (pin "11") (pinfunction "SCL_11") (pintype "passive"))
    )
    (net (code "89") (name "/PF2") (class "Default")
      (node (ref "J1") (pin "20") (pinfunction "20_20") (pintype "passive"))
      (node (ref "J16") (pin "2") (pinfunction "2_2") (pintype "passive"))
    )
    (net (code "90") (name "/PF3") (class "Default")
      (node (ref "J1") (pin "19") (pinfunction "19_19") (pintype "passive"))
      (node (ref "J17") (pin "2") (pinfunction "2_2") (pintype "passive"))
    )
    (net (code "91") (name "/PF4") (class "Default")
      (node (ref "J1") (pin "18") (pinfunction "18_18") (pintype "passive"))
      (node (ref "J18") (pin "2") (pinfunction "2_2") (pintype "passive"))
    )
    (net (code "92") (name "/PF5") (class "Default")
      (node (ref "J1") (pin "17") (pinfunction "17_17") (pintype "passive"))
      (node (ref "J19") (pin "2") (pinfunction "2_2") (pintype "passive"))
    )
    (net (code "93") (name "/PF6") (class "Default")
      (node (ref "J1") (pin "16") (pinfunction "16_16") (pintype "passive"))
    )
    (net (code "94") (name "/PF7") (class "Default")
      (node (ref "J1") (pin "15") (pinfunction "15_15") (pintype "passive"))
    )
    (net (code "95") (name "/PF8") (class "Default")
      (node (ref "J1") (pin "14") (pinfunction "14_14") (pintype "passive"))
    )
    (net (code "96") (name "/PF9") (class "Default")
      (node (ref "J1") (pin "13") (pinfunction "13_13") (pintype "passive"))
    )
    (net (code "97") (name "/PF10") (class "Default")
      (node (ref "J1") (pin "12") (pinfunction "12_12") (pintype "passive"))
    )
    (net (code "98") (name "/PF11") (class "Default")
      (node (ref "J1") (pin "43") (pinfunction "43_43") (pintype "passive"))
    )
    (net (code "99") (name "/PF12") (class "Default")
      (node (ref "J1") (pin "44") (pinfunction "44_44") (pintype "passive"))
    )
    (net (code "100") (name "/PF13") (class "Default")
      (node (ref "J1") (pin "45") (pinfunction "45_45") (pintype "passive"))
    )
    (net (code "101") (name "/PF14") (class "Default")
      (node (ref "J1") (pin "46") (pinfunction "46_46") (pintype "passive"))
    )
    (net (code "102") (name "/PF15") (class "Default")
      (node (ref "J1") (pin "47") (pinfunction "47_47") (pintype "passive"))
    )
    (net (code "103") (name "/PG0") (class "Default")
      (node (ref "J1") (pin "48") (pinfunction "48_48") (pintype "passive"))
    )
    (net (code "104") (name "/PG1") (class "Default")
      (node (ref "J1") (pin "49") (pinfunction "49_49") (pintype "passive"))
    )
    (net (code "105") (name "/PG2") (class "Default")
      (node (ref "J2") (pin "48") (pinfunction "48_48") (pintype "passive"))
    )
    (net (code "106") (name "/PG3") (class "Default")
      (node (ref "J2") (pin "47") (pinfunction "47_47") (pintype "passive"))
      (node (ref "J9") (pin "3") (pinfunction "3_3") (pintype "passive"))
    )
    (net (code "107") (name "/PG4") (class "Default")
      (node (ref "J2") (pin "46") (pinfunction "46_46") (pintype "passive"))
      (node (ref "J9") (pin "2") (pinfunction "2_2") (pintype "passive"))
    )
    (net (code "108") (name "/PG5") (class "Default")
      (node (ref "J10") (pin "3") (pinfunction "3_3") (pintype "passive"))
      (node (ref "J2") (pin "45") (pinfunction "45_45") (pintype "passive"))
    )
    (net (code "109") (name "/PG6") (class "Default")
      (node (ref "J10") (pin "2") (pinfunction "2_2") (pintype "passive"))
      (node (ref "J2") (pin "44") (pinfunction "44_44") (pintype "passive"))
    )
    (net (code "110") (name "/PG7") (class "Default")
      (node (ref "J14") (pin "3") (pinfunction "3_3") (pintype "passive"))
      (node (ref "J2") (pin "43") (pinfunction "43_43") (pintype "passive"))
    )
    (net (code "111") (name "/PG8") (class "Default")
      (node (ref "J14") (pin "2") (pinfunction "2_2") (pintype "passive"))
      (node (ref "J2") (pin "42") (pinfunction "42_42") (pintype "passive"))
    )
    (net (code "112") (name "/PG9") (class "Default")
      (node (ref "J2") (pin "14") (pinfunction "14_14") (pintype "passive"))
    )
    (net (code "113") (name "/PG10") (class "Default")
      (node (ref "J2") (pin "15") (pinfunction "15_15") (pintype "passive"))
    )
    (net (code "114") (name "/PG11") (class "Default")
      (node (ref "IC2") (pin "16") (pinfunction "TXEN_16") (pintype "passive"))
      (node (ref "J2") (pin "16") (pinfunction "16_16") (pintype "passive"))
    )
    (net (code "115") (name "/PG12") (class "Default")
      (node (ref "J2") (pin "17") (pinfunction "17_17") (pintype "passive"))
    )
    (net (code "116") (name "/PG13") (class "Default")
      (node (ref "IC2") (pin "17") (pinfunction "TXD0_17") (pintype "passive"))
      (node (ref "J2") (pin "18") (pinfunction "18_18") (pintype "passive"))
    )
    (net (code "117") (name "/PG14") (class "Default")
      (node (ref "IC2") (pin "18") (pinfunction "TXD1_18") (pintype "passive"))
      (node (ref "J2") (pin "19") (pinfunction "19_19") (pintype "passive"))
    )
    (net (code "118") (name "/PG15") (class "Default")
      (node (ref "J2") (pin "20") (pinfunction "20_20") (pintype "passive"))
    )
    (net (code "119") (name "/RS232_RX") (class "Default")
      (node (ref "IC1") (pin "8") (pinfunction "R2IN_8") (pintype "passive"))
      (node (ref "J8") (pin "3") (pinfunction "3_3") (pintype "passive"))
    )
    (net (code "120") (name "/RS232_TX") (class "Default")
      (node (ref "IC1") (pin "7") (pinfunction "T2OUT_7") (pintype "passive"))
      (node (ref "J8") (pin "2") (pinfunction "2_2") (pintype "passive"))
    )
    (net (code "121") (name "GBAT") (class "Default")
      (node (ref "C15") (pin "2") (pinfunction "2_2") (pintype "passive"))
      (node (ref "C25") (pin "2") (pinfunction "2_2") (pintype "passive"))
      (node (ref "D3") (pin "1") (pinfunction "1_1") (pintype "passive"))
      (node (ref "P1") (pin "2") (pinfunction "-_2") (pintype "passive"))
      (node (ref "P2") (pin "2") (pinfunction "-_2") (pintype "passive"))
      (node (ref "PS1") (pin "2") (pinfunction "GND_2") (pintype "passive"))
      (node (ref "PS2") (pin "2") (pinfunction "GND_2") (pintype "passive"))
    )
    (net (code "122") (name "GND") (class "Default")
      (node (ref "C1") (pin "2") (pinfunction "2_2") (pintype "passive"))
      (node (ref "C10") (pin "1") (pinfunction "1_1") (pintype "passive"))
      (node (ref "C11") (pin "2") (pinfunction "2_2") (pintype "passive"))
      (node (ref "C12") (pin "2") (pinfunction "2_2") (pintype "passive"))
      (node (ref "C13") (pin "1") (pinfunction "1_1") (pintype "passive"))
      (node (ref "C14") (pin "1") (pinfunction "1_1") (pintype "passive"))
      (node (ref "C16") (pin "2") (pinfunction "2_2") (pintype "passive"))
      (node (ref "C17") (pin "1") (pinfunction "1_1") (pintype "passive"))
      (node (ref "C18") (pin "1") (pinfunction "1_1") (pintype "passive"))
      (node (ref "C19") (pin "1") (pinfunction "1_1") (pintype "passive"))
      (node (ref "C2") (pin "2") (pinfunction "2_2") (pintype "passive"))
      (node (ref "C20") (pin "1") (pinfunction "1_1") (pintype "passive"))
      (node (ref "C21") (pin "1") (pinfunction "1_1") (pintype "passive"))
      (node (ref "C22") (pin "1") (pinfunction "1_1") (pintype "passive"))
      (node (ref "C23") (pin "1") (pinfunction "1_1") (pintype "passive"))
      (node (ref "C24") (pin "1") (pinfunction "1_1") (pintype "passive"))
      (node (ref "C26") (pin "2") (pinfunction "2_2") (pintype "passive"))
      (node (ref "C3") (pin "1") (pinfunction "1_1") (pintype "passive"))
      (node (ref "C6") (pin "1") (pinfunction "1_1") (pintype "passive"))
      (node (ref "C7") (pin "1") (pinfunction "1_1") (pintype "passive"))
      (node (ref "C8") (pin "2") (pinfunction "2_2") (pintype "passive"))
      (node (ref "C9") (pin "2") (pinfunction "2_2") (pintype "passive"))
      (node (ref "D1") (pin "1") (pinfunction "1_1") (pintype "passive"))
      (node (ref "D4") (pin "K") (pinfunction "K_K") (pintype "passive"))
      (node (ref "D5") (pin "K") (pinfunction "K_K") (pintype "passive"))
      (node (ref "D6") (pin "K") (pinfunction "K_K") (pintype "passive"))
      (node (ref "IC1") (pin "15") (pinfunction "GND_15") (pintype "passive"))
      (node (ref "IC2") (pin "25") (pinfunction "VSS_25") (pintype "passive"))
      (node (ref "J1") (pin "31") (pinfunction "31_31") (pintype "passive"))
      (node (ref "J1") (pin "32") (pinfunction "32_32") (pintype "passive"))
      (node (ref "J10") (pin "1") (pinfunction "1_1") (pintype "passive"))
      (node (ref "J12") (pin "1") (pinfunction "1_1") (pintype "passive"))
      (node (ref "J13") (pin "1") (pinfunction "1_1") (pintype "passive"))
      (node (ref "J14") (pin "1") (pinfunction "1_1") (pintype "passive"))
      (node (ref "J16") (pin "3") (pinfunction "3_3") (pintype "passive"))
      (node (ref "J17") (pin "3") (pinfunction "3_3") (pintype "passive"))
      (node (ref "J18") (pin "3") (pinfunction "3_3") (pintype "passive"))
      (node (ref "J19") (pin "3") (pinfunction "3_3") (pintype "passive"))
      (node (ref "J2") (pin "30") (pinfunction "30_30") (pintype "passive"))
      (node (ref "J2") (pin "31") (pinfunction "31_31") (pintype "passive"))
      (node (ref "J3") (pin "1") (pinfunction "1_1") (pintype "passive"))
      (node (ref "J4") (pin "1") (pinfunction "1_1") (pintype "passive"))
      (node (ref "J5") (pin "1") (pinfunction "1_1") (pintype "passive"))
      (node (ref "J6") (pin "1") (pinfunction "1_1") (pintype "passive"))
      (node (ref "J7") (pin "1") (pinfunction "1_1") (pintype "passive"))
      (node (ref "J8") (pin "5") (pinfunction "5_5") (pintype "passive"))
      (node (ref "J9") (pin "1") (pinfunction "1_1") (pintype "passive"))
      (node (ref "PS1") (pin "5") (pinfunction "0V_5") (pintype "passive"))
      (node (ref "PS2") (pin "6") (pinfunction "0V_6") (pintype "passive"))
      (node (ref "Q1") (pin "2") (pinfunction "E_2") (pintype "passive"))
      (node (ref "R20") (pin "1") (pinfunction "1_1") (pintype "passive"))
      (node (ref "R21") (pin "1") (pinfunction "1_1") (pintype "passive"))
      (node (ref "R23") (pin "2") (pinfunction "2_2") (pintype "passive"))
      (node (ref "R24") (pin "2") (pinfunction "2_2") (pintype "passive"))
      (node (ref "R4") (pin "1") (pinfunction "1_1") (pintype "passive"))
      (node (ref "R5") (pin "1") (pinfunction "1_1") (pintype "passive"))
      (node (ref "RJ1") (pin "7") (pinfunction "NC_7") (pintype "passive"))
      (node (ref "RJ1") (pin "8") (pinfunction "NC_8") (pintype "passive"))
      (node (ref "RJ1") (pin "MH1") (pinfunction "MH1_MH1") (pintype "passive"))
      (node (ref "RJ1") (pin "MH2") (pinfunction "MH2_MH2") (pintype "passive"))
      (node (ref "RJ1") (pin "MH3") (pinfunction "MH3_MH3") (pintype "passive"))
      (node (ref "RJ1") (pin "MH4") (pinfunction "MH4_MH4") (pintype "passive"))
      (node (ref "SW1") (pin "2") (pinfunction "2_2") (pintype "passive"))
      (node (ref "SW2") (pin "2") (pinfunction "2_2") (pintype "passive"))
      (node (ref "U1") (pin "8") (pinfunction "GND_8") (pintype "passive"))
      (node (ref "U2") (pin "2") (pinfunction "GND_2") (pintype "passive"))
      (node (ref "U2") (pin "8") (pinfunction "RS_8") (pintype "passive"))
      (node (ref "U3") (pin "2") (pinfunction "GND_2") (pintype "passive"))
      (node (ref "U3") (pin "8") (pinfunction "RS_8") (pintype "passive"))
      (node (ref "X1") (pin "2") (pinfunction "GND_2") (pintype "passive"))
    )
    (net (code "123") (name "Net-(BUZZER1--)") (class "Default")
      (node (ref "BUZZER1") (pin "2") (pinfunction "-_2") (pintype "passive"))
      (node (ref "Q1") (pin "3") (pinfunction "C_3") (pintype "passive"))
    )
    (net (code "124") (name "Net-(C8-Pad1)") (class "Default")
      (node (ref "C8") (pin "1") (pinfunction "1_1") (pintype "passive"))
      (node (ref "R6") (pin "2") (pinfunction "2_2") (pintype "passive"))
      (node (ref "R8") (pin "1") (pinfunction "1_1") (pintype "passive"))
    )
    (net (code "125") (name "Net-(C9-Pad1)") (class "Default")
      (node (ref "C9") (pin "1") (pinfunction "1_1") (pintype "passive"))
      (node (ref "R7") (pin "1") (pinfunction "1_1") (pintype "passive"))
      (node (ref "R9") (pin "2") (pinfunction "2_2") (pintype "passive"))
    )
    (net (code "126") (name "Net-(C11-Pad1)") (class "Default")
      (node (ref "C11") (pin "1") (pinfunction "1_1") (pintype "passive"))
      (node (ref "R10") (pin "2") (pinfunction "2_2") (pintype "passive"))
      (node (ref "R12") (pin "1") (pinfunction "1_1") (pintype "passive"))
    )
    (net (code "127") (name "Net-(C12-Pad1)") (class "Default")
      (node (ref "C12") (pin "1") (pinfunction "1_1") (pintype "passive"))
      (node (ref "R11") (pin "1") (pinfunction "1_1") (pintype "passive"))
      (node (ref "R13") (pin "2") (pinfunction "2_2") (pintype "passive"))
    )
    (net (code "128") (name "Net-(D1-Pad2)") (class "Default")
      (node (ref "D1") (pin "2") (pinfunction "2_2") (pintype "passive"))
      (node (ref "J8") (pin "MH1") (pinfunction "MH1_MH1") (pintype "passive"))
      (node (ref "J8") (pin "MH2") (pinfunction "MH2_MH2") (pintype "passive"))
      (node (ref "R4") (pin "2") (pinfunction "2_2") (pintype "passive"))
    )
    (net (code "129") (name "Net-(D2-A)") (class "Default")
      (node (ref "D2") (pin "1") (pinfunction "A_1") (pintype "passive"))
      (node (ref "D3") (pin "2") (pinfunction "2_2") (pintype "passive"))
      (node (ref "F1") (pin "2") (pinfunction "2_2") (pintype "passive"))
    )
    (net (code "130") (name "Net-(D4-PadA)") (class "Default")
      (node (ref "D4") (pin "A") (pinfunction "A_A") (pintype "passive"))
      (node (ref "R19") (pin "1") (pinfunction "1_1") (pintype "passive"))
    )
    (net (code "131") (name "Net-(D5-PadA)") (class "Default")
      (node (ref "D5") (pin "A") (pinfunction "A_A") (pintype "passive"))
      (node (ref "R22") (pin "1") (pinfunction "1_1") (pintype "passive"))
    )
    (net (code "132") (name "Net-(D6-PadA)") (class "Default")
      (node (ref "D6") (pin "A") (pinfunction "A_A") (pintype "passive"))
      (node (ref "R25") (pin "1") (pinfunction "1_1") (pintype "passive"))
    )
    (net (code "133") (name "Net-(IC1-C1+)") (class "Default")
      (node (ref "C4") (pin "2") (pinfunction "2_2") (pintype "passive"))
      (node (ref "IC1") (pin "1") (pinfunction "C1+_1") (pintype "passive"))
    )
    (net (code "134") (name "Net-(IC1-C1-)") (class "Default")
      (node (ref "C4") (pin "1") (pinfunction "1_1") (pintype "passive"))
      (node (ref "IC1") (pin "3") (pinfunction "C1-_3") (pintype "passive"))
    )
    (net (code "135") (name "Net-(IC1-C2+)") (class "Default")
      (node (ref "C5") (pin "2") (pinfunction "2_2") (pintype "passive"))
      (node (ref "IC1") (pin "4") (pinfunction "C2+_4") (pintype "passive"))
    )
    (net (code "136") (name "Net-(IC1-C2-)") (class "Default")
      (node (ref "C5") (pin "1") (pinfunction "1_1") (pintype "passive"))
      (node (ref "IC1") (pin "5") (pinfunction "C2-_5") (pintype "passive"))
    )
    (net (code "137") (name "Net-(IC1-V+)") (class "Default")
      (node (ref "C6") (pin "2") (pinfunction "2_2") (pintype "passive"))
      (node (ref "IC1") (pin "2") (pinfunction "V+_2") (pintype "passive"))
    )
    (net (code "138") (name "Net-(IC1-V-)") (class "Default")
      (node (ref "C7") (pin "2") (pinfunction "2_2") (pintype "passive"))
      (node (ref "IC1") (pin "6") (pinfunction "V-_6") (pintype "passive"))
    )
    (net (code "139") (name "Net-(IC2-MDIO)") (class "Default")
      (node (ref "IC2") (pin "12") (pinfunction "MDIO_12") (pintype "passive"))
      (node (ref "R18") (pin "1") (pinfunction "1_1") (pintype "passive"))
    )
    (net (code "140") (name "Net-(IC2-RBIAS)") (class "Default")
      (node (ref "IC2") (pin "24") (pinfunction "RBIAS_24") (pintype "passive"))
      (node (ref "R24") (pin "1") (pinfunction "1_1") (pintype "passive"))
    )
    (net (code "141") (name "Net-(IC2-RXN)") (class "Default")
      (node (ref "C23") (pin "2") (pinfunction "2_2") (pintype "passive"))
      (node (ref "IC2") (pin "22") (pinfunction "RXN_22") (pintype "passive"))
      (node (ref "R17") (pin "1") (pinfunction "1_1") (pintype "passive"))
      (node (ref "RJ1") (pin "6") (pinfunction "RD-_6") (pintype "passive"))
    )
    (net (code "142") (name "Net-(IC2-RXP)") (class "Default")
      (node (ref "C22") (pin "2") (pinfunction "2_2") (pintype "passive"))
      (node (ref "IC2") (pin "23") (pinfunction "RXP_23") (pintype "passive"))
      (node (ref "R16") (pin "1") (pinfunction "1_1") (pintype "passive"))
      (node (ref "RJ1") (pin "3") (pinfunction "RD+_3") (pintype "passive"))
    )
    (net (code "143") (name "Net-(IC2-TXN)") (class "Default")
      (node (ref "C21") (pin "2") (pinfunction "2_2") (pintype "passive"))
      (node (ref "IC2") (pin "20") (pinfunction "TXN_20") (pintype "passive"))
      (node (ref "R15") (pin "1") (pinfunction "1_1") (pintype "passive"))
      (node (ref "RJ1") (pin "2") (pinfunction "TD-_2") (pintype "passive"))
    )
    (net (code "144") (name "Net-(IC2-TXP)") (class "Default")
      (node (ref "C20") (pin "2") (pinfunction "2_2") (pintype "passive"))
      (node (ref "IC2") (pin "21") (pinfunction "TXP_21") (pintype "passive"))
      (node (ref "R14") (pin "1") (pinfunction "1_1") (pintype "passive"))
      (node (ref "RJ1") (pin "1") (pinfunction "TD+_1") (pintype "passive"))
    )
    (net (code "145") (name "Net-(IC2-XTAL1{slash}CLKIN)") (class "Default")
      (node (ref "IC2") (pin "5") (pinfunction "XTAL1/CLKIN_5") (pintype "passive"))
      (node (ref "X1") (pin "3") (pinfunction "OSC2_3") (pintype "passive"))
    )
    (net (code "146") (name "Net-(IC2-XTAL2)") (class "Default")
      (node (ref "IC2") (pin "4") (pinfunction "XTAL2_4") (pintype "passive"))
      (node (ref "X1") (pin "1") (pinfunction "OSC1_1") (pintype "passive"))
    )
    (net (code "147") (name "Net-(P1-+)") (class "Default")
      (node (ref "F1") (pin "1") (pinfunction "1_1") (pintype "passive"))
      (node (ref "P1") (pin "1") (pinfunction "+_1") (pintype "passive"))
      (node (ref "P2") (pin "1") (pinfunction "+_1") (pintype "passive"))
    )
    (net (code "148") (name "Net-(Q1-B)") (class "Default")
      (node (ref "Q1") (pin "1") (pinfunction "B_1") (pintype "passive"))
      (node (ref "R3") (pin "2") (pinfunction "2_2") (pintype "passive"))
      (node (ref "R5") (pin "2") (pinfunction "2_2") (pintype "passive"))
    )
    (net (code "149") (name "Net-(RJ1-LED(Y)_A)") (class "Default")
      (node (ref "R20") (pin "2") (pinfunction "2_2") (pintype "passive"))
      (node (ref "RJ1") (pin "12") (pinfunction "LED(Y)_A_12") (pintype "passive"))
    )
    (net (code "150") (name "Net-(RJ1-LED(Y)_K)") (class "Default")
      (node (ref "R21") (pin "2") (pinfunction "2_2") (pintype "passive"))
      (node (ref "RJ1") (pin "11") (pinfunction "LED(Y)_K_11") (pintype "passive"))
    )
    (net (code "151") (name "VBAT") (class "Default")
      (node (ref "C15") (pin "1") (pinfunction "1_1") (pintype "passive"))
      (node (ref "C25") (pin "1") (pinfunction "1_1") (pintype "passive"))
      (node (ref "D2") (pin "2") (pinfunction "K_2") (pintype "passive"))
      (node (ref "PS1") (pin "3") (pinfunction "VIN_3") (pintype "passive"))
      (node (ref "PS2") (pin "3") (pinfunction "VIN_3") (pintype "passive"))
    )
    (net (code "152") (name "VCC_3V3") (class "Default")
      (node (ref "C18") (pin "2") (pinfunction "2_2") (pintype "passive"))
      (node (ref "IC2") (pin "9") (pinfunction "VDDIO_9") (pintype "passive"))
      (node (ref "J1") (pin "3") (pinfunction "3_3") (pintype "passive"))
      (node (ref "J1") (pin "4") (pinfunction "4_4") (pintype "passive"))
      (node (ref "L1") (pin "1") (pinfunction "1_1") (pintype "passive"))
    )
    (net (code "153") (name "VCC_3V3E") (class "Default")
      (node (ref "C19") (pin "2") (pinfunction "2_2") (pintype "passive"))
      (node (ref "C24") (pin "2") (pinfunction "2_2") (pintype "passive"))
      (node (ref "IC2") (pin "1") (pinfunction "VDD2A_1") (pintype "passive"))
      (node (ref "IC2") (pin "19") (pinfunction "VDD1A_19") (pintype "passive"))
      (node (ref "L1") (pin "2") (pinfunction "2_2") (pintype "passive"))
      (node (ref "R14") (pin "2") (pinfunction "2_2") (pintype "passive"))
      (node (ref "R15") (pin "2") (pinfunction "2_2") (pintype "passive"))
      (node (ref "R16") (pin "2") (pinfunction "2_2") (pintype "passive"))
      (node (ref "R17") (pin "2") (pinfunction "2_2") (pintype "passive"))
      (node (ref "RJ1") (pin "4") (pinfunction "TCT_4") (pintype "passive"))
      (node (ref "RJ1") (pin "5") (pinfunction "RCT_5") (pintype "passive"))
    )
    (net (code "154") (name "VCC_5V") (class "Default")
      (node (ref "C1") (pin "1") (pinfunction "1_1") (pintype "passive"))
      (node (ref "C10") (pin "2") (pinfunction "2_2") (pintype "passive"))
      (node (ref "C13") (pin "2") (pinfunction "2_2") (pintype "passive"))
      (node (ref "C2") (pin "1") (pinfunction "1_1") (pintype "passive"))
      (node (ref "C26") (pin "1") (pinfunction "1_1") (pintype "passive"))
      (node (ref "C3") (pin "2") (pinfunction "2_2") (pintype "passive"))
      (node (ref "IC1") (pin "16") (pinfunction "VCC_16") (pintype "passive"))
      (node (ref "J1") (pin "1") (pinfunction "1_1") (pintype "passive"))
      (node (ref "J1") (pin "2") (pinfunction "2_2") (pintype "passive"))
      (node (ref "J10") (pin "4") (pinfunction "4_4") (pintype "passive"))
      (node (ref "J14") (pin "4") (pinfunction "4_4") (pintype "passive"))
      (node (ref "J3") (pin "4") (pinfunction "4_4") (pintype "passive"))
      (node (ref "J4") (pin "4") (pinfunction "4_4") (pintype "passive"))
      (node (ref "J5") (pin "4") (pinfunction "4_4") (pintype "passive"))
      (node (ref "J6") (pin "4") (pinfunction "4_4") (pintype "passive"))
      (node (ref "J7") (pin "4") (pinfunction "4_4") (pintype "passive"))
      (node (ref "J9") (pin "4") (pinfunction "4_4") (pintype "passive"))
      (node (ref "PS2") (pin "1") (pinfunction "CTRL_1") (pintype "passive"))
      (node (ref "PS2") (pin "4") (pinfunction "+VO_4") (pintype "passive"))
      (node (ref "R1") (pin "2") (pinfunction "2_2") (pintype "passive"))
      (node (ref "R2") (pin "2") (pinfunction "2_2") (pintype "passive"))
      (node (ref "U1") (pin "1") (pinfunction "VCC_1") (pintype "passive"))
      (node (ref "U2") (pin "3") (pinfunction "VCC_3") (pintype "passive"))
      (node (ref "U3") (pin "3") (pinfunction "VCC_3") (pintype "passive"))
    )
    (net (code "155") (name "VCC_12V") (class "Default")
      (node (ref "BUZZER1") (pin "1") (pinfunction "+_1") (pintype "passive"))
      (node (ref "C16") (pin "1") (pinfunction "1_1") (pintype "passive"))
      (node (ref "J12") (pin "2") (pinfunction "2_2") (pintype "passive"))
      (node (ref "J13") (pin "2") (pinfunction "2_2") (pintype "passive"))
      (node (ref "J16") (pin "1") (pinfunction "1_1") (pintype "passive"))
      (node (ref "J17") (pin "1") (pinfunction "1_1") (pintype "passive"))
      (node (ref "J18") (pin "1") (pinfunction "1_1") (pintype "passive"))
      (node (ref "J19") (pin "1") (pinfunction "1_1") (pintype "passive"))
      (node (ref "PS1") (pin "1") (pinfunction "CTRL_1") (pintype "passive"))
      (node (ref "PS1") (pin "4") (pinfunction "+VO_4") (pintype "passive"))
    )
    (net (code "156") (name "unconnected-(IC1-R1IN-Pad13)") (class "Default")
      (node (ref "IC1") (pin "13") (pinfunction "R1IN_13") (pintype "passive+no_connect"))
    )
    (net (code "157") (name "unconnected-(IC1-R1OUT-Pad12)") (class "Default")
      (node (ref "IC1") (pin "12") (pinfunction "R1OUT_12") (pintype "passive+no_connect"))
    )
    (net (code "158") (name "unconnected-(IC1-T1IN-Pad11)") (class "Default")
      (node (ref "IC1") (pin "11") (pinfunction "T1IN_11") (pintype "passive+no_connect"))
    )
    (net (code "159") (name "unconnected-(IC1-T1OUT-Pad14)") (class "Default")
      (node (ref "IC1") (pin "14") (pinfunction "T1OUT_14") (pintype "passive+no_connect"))
    )
    (net (code "160") (name "unconnected-(IC2-RXER{slash}~{PHYAD0}-Pad10)") (class "Default")
      (node (ref "IC2") (pin "10") (pinfunction "RXER/~{PHYAD0}_10") (pintype "passive+no_connect"))
    )
    (net (code "161") (name "unconnected-(IC2-VDDCR-Pad6)") (class "Default")
      (node (ref "IC2") (pin "6") (pinfunction "VDDCR_6") (pintype "passive+no_connect"))
    )
    (net (code "162") (name "unconnected-(J8-Pad1)") (class "Default")
      (node (ref "J8") (pin "1") (pinfunction "1_1") (pintype "passive+no_connect"))
    )
    (net (code "163") (name "unconnected-(J8-Pad4)") (class "Default")
      (node (ref "J8") (pin "4") (pinfunction "4_4") (pintype "passive+no_connect"))
    )
    (net (code "164") (name "unconnected-(J8-Pad6)") (class "Default")
      (node (ref "J8") (pin "6") (pinfunction "6_6") (pintype "passive+no_connect"))
    )
    (net (code "165") (name "unconnected-(J8-Pad7)") (class "Default")
      (node (ref "J8") (pin "7") (pinfunction "7_7") (pintype "passive+no_connect"))
    )
    (net (code "166") (name "unconnected-(J8-Pad8)") (class "Default")
      (node (ref "J8") (pin "8") (pinfunction "8_8") (pintype "passive+no_connect"))
    )
    (net (code "167") (name "unconnected-(J8-Pad9)") (class "Default")
      (node (ref "J8") (pin "9") (pinfunction "9_9") (pintype "passive+no_connect"))
    )
    (net (code "168") (name "unconnected-(PS1-TRIM-Pad6)") (class "Default")
      (node (ref "PS1") (pin "6") (pinfunction "TRIM_6") (pintype "passive+no_connect"))
    )
    (net (code "169") (name "unconnected-(PS2-TRIM-Pad5)") (class "Default")
      (node (ref "PS2") (pin "5") (pinfunction "TRIM_5") (pintype "passive+no_connect"))
    )
    (net (code "170") (name "unconnected-(U1-D0-Pad2)") (class "Default")
      (node (ref "U1") (pin "2") (pinfunction "D0_2") (pintype "passive+no_connect"))
    )
    (net (code "171") (name "unconnected-(U1-D1-Pad3)") (class "Default")
      (node (ref "U1") (pin "3") (pinfunction "D1_3") (pintype "passive+no_connect"))
    )
    (net (code "172") (name "unconnected-(U1-D2-Pad4)") (class "Default")
      (node (ref "U1") (pin "4") (pinfunction "D2_4") (pintype "passive+no_connect"))
    )
    (net (code "173") (name "unconnected-(U1-D3-Pad5)") (class "Default")
      (node (ref "U1") (pin "5") (pinfunction "D3_5") (pintype "passive+no_connect"))
    )
    (net (code "174") (name "unconnected-(U1-D4-Pad6)") (class "Default")
      (node (ref "U1") (pin "6") (pinfunction "D4_6") (pintype "passive+no_connect"))
    )
    (net (code "175") (name "unconnected-(U1-D5-Pad7)") (class "Default")
      (node (ref "U1") (pin "7") (pinfunction "D5_7") (pintype "passive+no_connect"))
    )
    (net (code "176") (name "unconnected-(U1-RX-Pad13)") (class "Default")
      (node (ref "U1") (pin "13") (pinfunction "RX_13") (pintype "passive+no_connect"))
    )
    (net (code "177") (name "unconnected-(U1-SWCLK-Pad9)") (class "Default")
      (node (ref "U1") (pin "9") (pinfunction "SWCLK_9") (pintype "passive+no_connect"))
    )
    (net (code "178") (name "unconnected-(U1-SWDIO-Pad10)") (class "Default")
      (node (ref "U1") (pin "10") (pinfunction "SWDIO_10") (pintype "passive+no_connect"))
    )
    (net (code "179") (name "unconnected-(U1-TX-Pad14)") (class "Default")
      (node (ref "U1") (pin "14") (pinfunction "TX_14") (pintype "passive+no_connect"))
    )
    (net (code "180") (name "unconnected-(U2-Vref-Pad5)") (class "Default")
      (node (ref "U2") (pin "5") (pinfunction "Vref_5") (pintype "passive+no_connect"))
    )
    (net (code "181") (name "unconnected-(U3-Vref-Pad5)") (class "Default")
      (node (ref "U3") (pin "5") (pinfunction "Vref_5") (pintype "passive+no_connect"))
    )
  )
)
